# pentabug.net
KiCad netlist of a schematic drawn in EAGLE
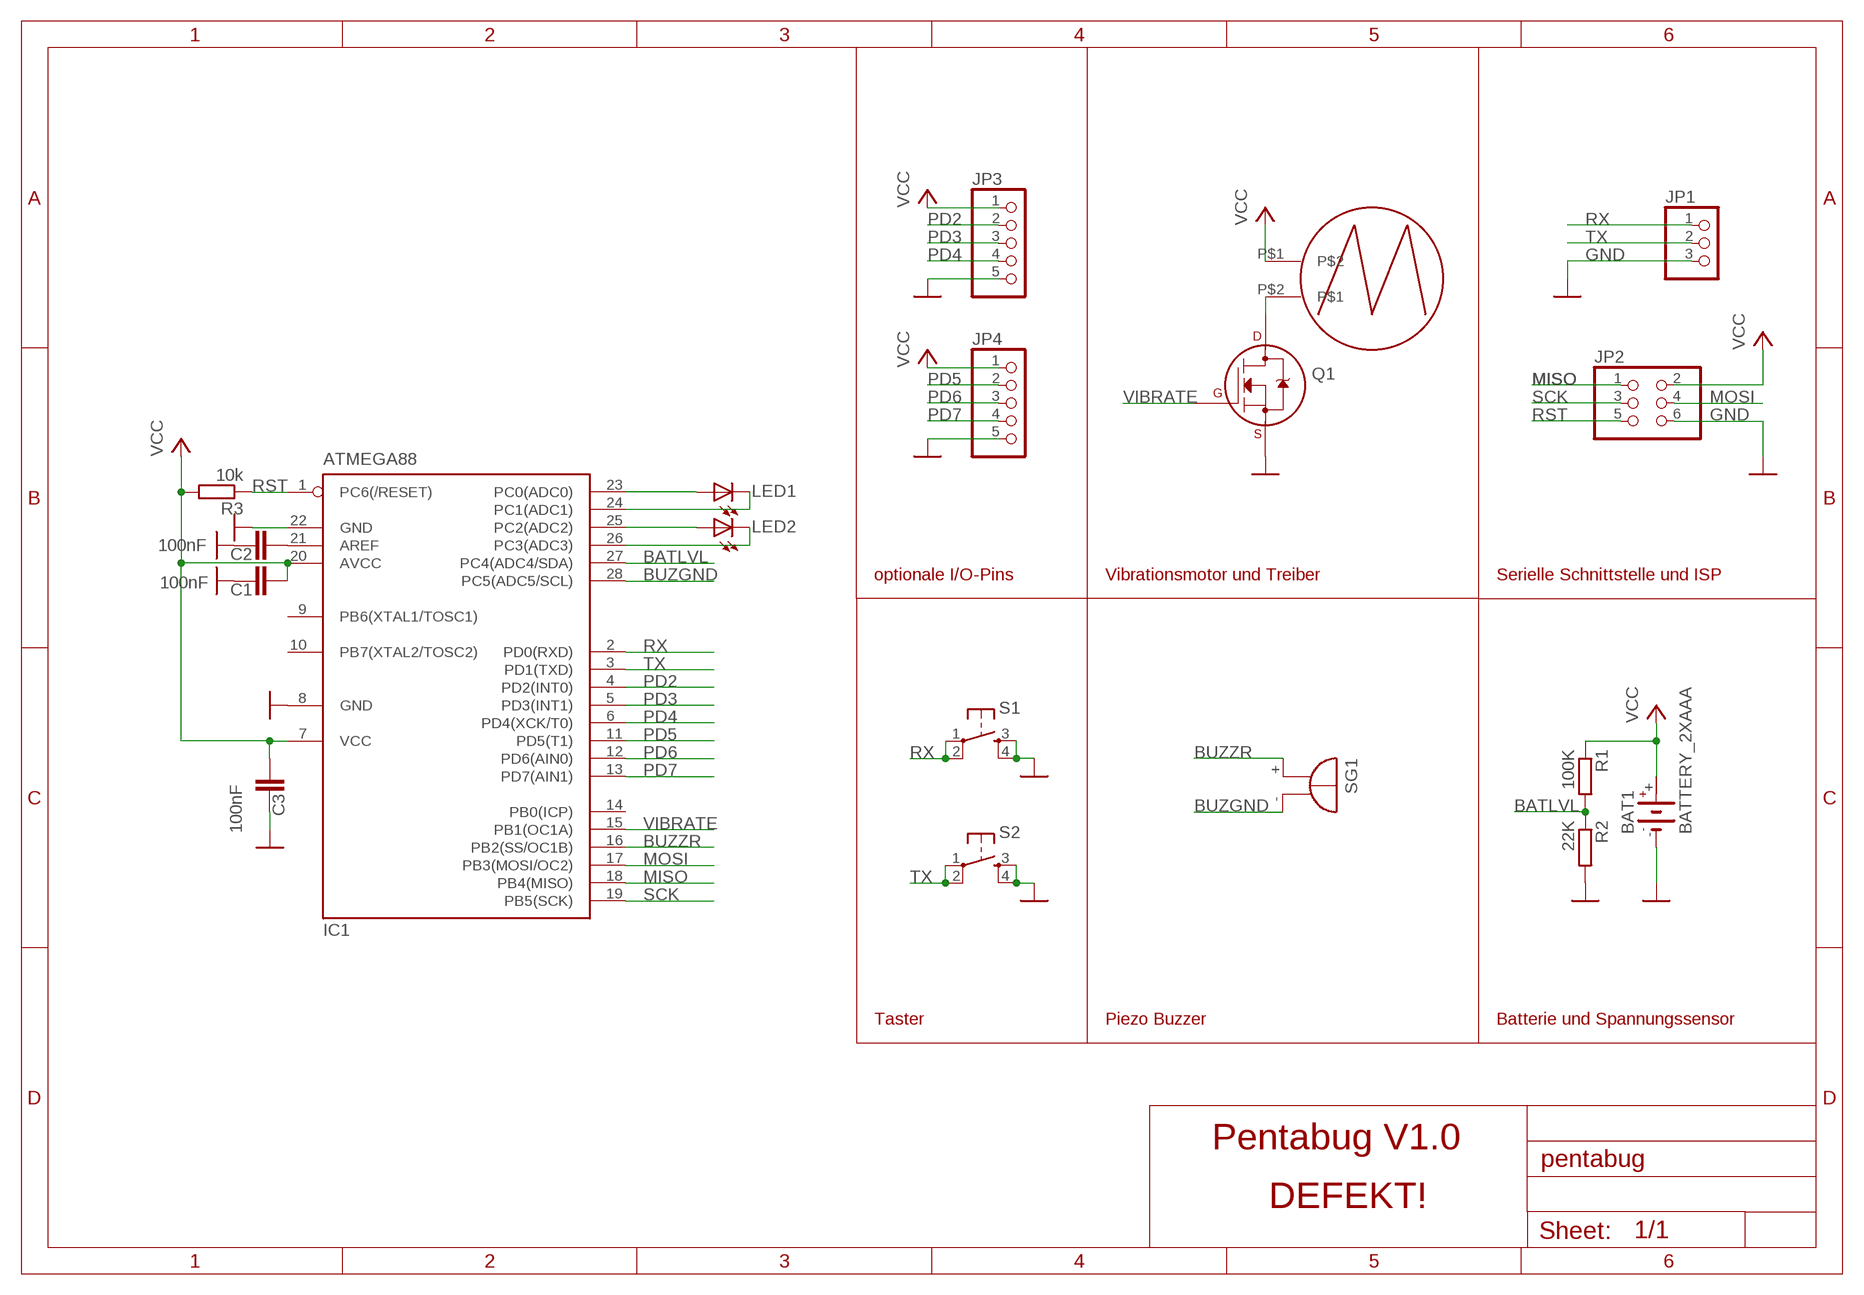
[diagram p0: schematic, sheet 1]

(export (version "E")
  (design (tool "Eeschema 10.0.6"))
  (components
    (comp (ref "BAT1")
      (value "BATTERY_2XAAA")
      (footprint "eagle-import:BATTERY_2XAAA")
      (libsource (lib "eagle-import") (part "BATTERY_2XAAA"))
    )
    (comp (ref "C1")
      (value "100nF")
      (footprint "eagle-import:C025-024X044")
      (libsource (lib "eagle-import") (part "C-EU025-024X044"))
    )
    (comp (ref "C2")
      (value "100nF")
      (footprint "eagle-import:C025-024X044")
      (libsource (lib "eagle-import") (part "C-EU025-024X044"))
    )
    (comp (ref "C3")
      (value "100nF")
      (footprint "eagle-import:C025-024X044")
      (libsource (lib "eagle-import") (part "C-EU025-024X044"))
    )
    (comp (ref "IC1")
      (value "ATMEGA88")
      (footprint "eagle-import:DIL28-3")
      (libsource (lib "eagle-import") (part "MEGA8-P"))
    )
    (comp (ref "JP1")
      (value "PINHD-1X3")
      (footprint "eagle-import:1X03")
      (libsource (lib "eagle-import") (part "PINHD-1X3"))
    )
    (comp (ref "JP2")
      (value "PINHD-2X3")
      (footprint "eagle-import:2X03")
      (libsource (lib "eagle-import") (part "PINHD-2X3"))
    )
    (comp (ref "JP3")
      (value "PINHD-1X5")
      (footprint "eagle-import:1X05")
      (libsource (lib "eagle-import") (part "PINHD-1X5"))
    )
    (comp (ref "JP4")
      (value "PINHD-1X5")
      (footprint "eagle-import:1X05")
      (libsource (lib "eagle-import") (part "PINHD-1X5"))
    )
    (comp (ref "LED1")
      (value "LED5MM")
      (footprint "eagle-import:LED5MM")
      (libsource (lib "eagle-import") (part "LED5MM"))
    )
    (comp (ref "LED2")
      (value "LED5MM")
      (footprint "eagle-import:LED5MM")
      (libsource (lib "eagle-import") (part "LED5MM"))
    )
    (comp (ref "Q1")
      (value "2N7000_TO92")
      (footprint "eagle-import:TO-92")
      (libsource (lib "eagle-import") (part "2N700_TO920"))
    )
    (comp (ref "R1")
      (value "100K")
      (footprint "eagle-import:0207_10")
      (libsource (lib "eagle-import") (part "R-EU_0207/10"))
    )
    (comp (ref "R2")
      (value "22K")
      (footprint "eagle-import:0207_10")
      (libsource (lib "eagle-import") (part "R-EU_0207/10"))
    )
    (comp (ref "R3")
      (value "10k")
      (footprint "eagle-import:0207_10")
      (libsource (lib "eagle-import") (part "R-EU_0207/10"))
    )
    (comp (ref "S1")
      (value "TAC_SWITCHPTH")
      (footprint "eagle-import:TACTILE-PTH")
      (libsource (lib "eagle-import") (part "TAC_SWITCHPTH"))
    )
    (comp (ref "S2")
      (value "TAC_SWITCHPTH")
      (footprint "eagle-import:TACTILE-PTH")
      (libsource (lib "eagle-import") (part "TAC_SWITCHPTH"))
    )
    (comp (ref "SG1")
      (value "MULTIBUZZRTDKBUZZR")
      (footprint "eagle-import:BUZZRTDK")
      (libsource (lib "eagle-import") (part "MULTIBUZZRTDKBUZZR"))
    )
    (comp (ref "U$1")
      (value "VIBRAMOTOR")
      (footprint "eagle-import:LA4-432")
      (libsource (lib "eagle-import") (part "VIBRAMOTOR"))
    )
  )
  (nets
    (net (code "1") (name "/BATLVL") (class "Default")
      (node (ref "IC1") (pin "27") (pinfunction "PC4(ADC4/SDA)_27") (pintype "bidirectional"))
      (node (ref "R1") (pin "2") (pinfunction "2_2") (pintype "passive"))
      (node (ref "R2") (pin "1") (pinfunction "1_1") (pintype "passive"))
    )
    (net (code "2") (name "/BUZGND") (class "Default")
      (node (ref "IC1") (pin "28") (pinfunction "PC5(ADC5/SCL)_28") (pintype "bidirectional"))
      (node (ref "SG1") (pin "-") (pinfunction "-_-") (pintype "passive"))
    )
    (net (code "3") (name "/BUZZR") (class "Default")
      (node (ref "IC1") (pin "16") (pinfunction "PB2(SS/OC1B)_16") (pintype "bidirectional"))
      (node (ref "SG1") (pin "+") (pinfunction "+_+") (pintype "passive"))
    )
    (net (code "4") (name "/MISO") (class "Default")
      (node (ref "IC1") (pin "18") (pinfunction "PB4(MISO)_18") (pintype "bidirectional"))
      (node (ref "JP2") (pin "1") (pinfunction "1_1") (pintype "passive"))
    )
    (net (code "5") (name "/MOSI") (class "Default")
      (node (ref "IC1") (pin "17") (pinfunction "PB3(MOSI/OC2)_17") (pintype "bidirectional"))
      (node (ref "JP2") (pin "4") (pinfunction "4_4") (pintype "passive"))
    )
    (net (code "6") (name "/PD2") (class "Default")
      (node (ref "IC1") (pin "4") (pinfunction "PD2(INT0)_4") (pintype "bidirectional"))
      (node (ref "JP3") (pin "2") (pinfunction "2_2") (pintype "passive"))
    )
    (net (code "7") (name "/PD3") (class "Default")
      (node (ref "IC1") (pin "5") (pinfunction "PD3(INT1)_5") (pintype "bidirectional"))
      (node (ref "JP3") (pin "3") (pinfunction "3_3") (pintype "passive"))
    )
    (net (code "8") (name "/PD4") (class "Default")
      (node (ref "IC1") (pin "6") (pinfunction "PD4(XCK/T0)_6") (pintype "bidirectional"))
      (node (ref "JP3") (pin "4") (pinfunction "4_4") (pintype "passive"))
    )
    (net (code "9") (name "/PD5") (class "Default")
      (node (ref "IC1") (pin "11") (pinfunction "PD5(T1)_11") (pintype "bidirectional"))
      (node (ref "JP4") (pin "2") (pinfunction "2_2") (pintype "passive"))
    )
    (net (code "10") (name "/PD6") (class "Default")
      (node (ref "IC1") (pin "12") (pinfunction "PD6(AIN0)_12") (pintype "bidirectional"))
      (node (ref "JP4") (pin "3") (pinfunction "3_3") (pintype "passive"))
    )
    (net (code "11") (name "/PD7") (class "Default")
      (node (ref "IC1") (pin "13") (pinfunction "PD7(AIN1)_13") (pintype "bidirectional"))
      (node (ref "JP4") (pin "4") (pinfunction "4_4") (pintype "passive"))
    )
    (net (code "12") (name "/RST") (class "Default")
      (node (ref "IC1") (pin "1") (pinfunction "PC6(/RESET)_1") (pintype "bidirectional"))
      (node (ref "JP2") (pin "5") (pinfunction "5_5") (pintype "passive"))
      (node (ref "R3") (pin "1") (pinfunction "1_1") (pintype "passive"))
    )
    (net (code "13") (name "/RX") (class "Default")
      (node (ref "IC1") (pin "2") (pinfunction "PD0(RXD)_2") (pintype "bidirectional"))
      (node (ref "JP1") (pin "1") (pinfunction "1_1") (pintype "passive"))
      (node (ref "S1") (pin "1") (pinfunction "1_1") (pintype "passive"))
      (node (ref "S1") (pin "2") (pinfunction "2_2") (pintype "passive"))
    )
    (net (code "14") (name "/SCK") (class "Default")
      (node (ref "IC1") (pin "19") (pinfunction "PB5(SCK)_19") (pintype "bidirectional"))
      (node (ref "JP2") (pin "3") (pinfunction "3_3") (pintype "passive"))
    )
    (net (code "15") (name "/TX") (class "Default")
      (node (ref "IC1") (pin "3") (pinfunction "PD1(TXD)_3") (pintype "bidirectional"))
      (node (ref "JP1") (pin "2") (pinfunction "2_2") (pintype "passive"))
      (node (ref "S2") (pin "1") (pinfunction "1_1") (pintype "passive"))
      (node (ref "S2") (pin "2") (pinfunction "2_2") (pintype "passive"))
    )
    (net (code "16") (name "/VIBRATE") (class "Default")
      (node (ref "IC1") (pin "15") (pinfunction "PB1(OC1A)_15") (pintype "bidirectional"))
      (node (ref "Q1") (pin "2") (pinfunction "G_2") (pintype "tri_state"))
    )
    (net (code "17") (name "GND") (class "Default")
      (node (ref "BAT1") (pin "-") (pinfunction "-_-") (pintype "passive"))
      (node (ref "C1") (pin "1") (pinfunction "1_1") (pintype "passive"))
      (node (ref "C2") (pin "1") (pinfunction "1_1") (pintype "passive"))
      (node (ref "C3") (pin "1") (pinfunction "1_1") (pintype "passive"))
      (node (ref "IC1") (pin "22") (pinfunction "GND_22") (pintype "power_in"))
      (node (ref "IC1") (pin "8") (pinfunction "GND_8") (pintype "power_in"))
      (node (ref "JP1") (pin "3") (pinfunction "3_3") (pintype "passive"))
      (node (ref "JP2") (pin "6") (pinfunction "6_6") (pintype "passive"))
      (node (ref "JP3") (pin "5") (pinfunction "5_5") (pintype "passive"))
      (node (ref "JP4") (pin "5") (pinfunction "5_5") (pintype "passive"))
      (node (ref "Q1") (pin "1") (pinfunction "S_1") (pintype "bidirectional"))
      (node (ref "R2") (pin "2") (pinfunction "2_2") (pintype "passive"))
      (node (ref "S1") (pin "3") (pinfunction "3_3") (pintype "passive"))
      (node (ref "S1") (pin "4") (pinfunction "4_4") (pintype "passive"))
      (node (ref "S2") (pin "3") (pinfunction "3_3") (pintype "passive"))
      (node (ref "S2") (pin "4") (pinfunction "4_4") (pintype "passive"))
    )
    (net (code "18") (name "Net-(IC1-AREF)") (class "Default")
      (node (ref "C2") (pin "2") (pinfunction "2_2") (pintype "passive"))
      (node (ref "IC1") (pin "21") (pinfunction "AREF_21") (pintype "passive"))
    )
    (net (code "19") (name "Net-(IC1-PC0(ADC0))") (class "Default")
      (node (ref "IC1") (pin "23") (pinfunction "PC0(ADC0)_23") (pintype "bidirectional"))
      (node (ref "LED1") (pin "A") (pinfunction "A_A") (pintype "passive"))
    )
    (net (code "20") (name "Net-(IC1-PC1(ADC1))") (class "Default")
      (node (ref "IC1") (pin "24") (pinfunction "PC1(ADC1)_24") (pintype "bidirectional"))
      (node (ref "LED1") (pin "K") (pinfunction "C_K") (pintype "passive"))
    )
    (net (code "21") (name "Net-(IC1-PC2(ADC2))") (class "Default")
      (node (ref "IC1") (pin "25") (pinfunction "PC2(ADC2)_25") (pintype "bidirectional"))
      (node (ref "LED2") (pin "A") (pinfunction "A_A") (pintype "passive"))
    )
    (net (code "22") (name "Net-(IC1-PC3(ADC3))") (class "Default")
      (node (ref "IC1") (pin "26") (pinfunction "PC3(ADC3)_26") (pintype "bidirectional"))
      (node (ref "LED2") (pin "K") (pinfunction "C_K") (pintype "passive"))
    )
    (net (code "23") (name "Net-(Q1-D)") (class "Default")
      (node (ref "Q1") (pin "3") (pinfunction "D_3") (pintype "bidirectional"))
      (node (ref "U$1") (pin "P$2") (pinfunction "P$1_P$2") (pintype "power_in"))
    )
    (net (code "24") (name "VCC") (class "Default")
      (node (ref "BAT1") (pin "+") (pinfunction "+_+") (pintype "passive"))
      (node (ref "C1") (pin "2") (pinfunction "2_2") (pintype "passive"))
      (node (ref "C3") (pin "2") (pinfunction "2_2") (pintype "passive"))
      (node (ref "IC1") (pin "20") (pinfunction "AVCC_20") (pintype "power_in"))
      (node (ref "IC1") (pin "7") (pinfunction "VCC_7") (pintype "power_in"))
      (node (ref "JP2") (pin "2") (pinfunction "2_2") (pintype "passive"))
      (node (ref "JP3") (pin "1") (pinfunction "1_1") (pintype "passive"))
      (node (ref "JP4") (pin "1") (pinfunction "1_1") (pintype "passive"))
      (node (ref "R1") (pin "1") (pinfunction "1_1") (pintype "passive"))
      (node (ref "R3") (pin "2") (pinfunction "2_2") (pintype "passive"))
      (node (ref "U$1") (pin "P$1") (pinfunction "P$2_P$1") (pintype "power_in"))
    )
    (net (code "25") (name "unconnected-(IC1-PB0(ICP)-Pad14)") (class "Default")
      (node (ref "IC1") (pin "14") (pinfunction "PB0(ICP)_14") (pintype "bidirectional"))
    )
    (net (code "26") (name "unconnected-(IC1-PB6(XTAL1{slash}TOSC1)-Pad9)") (class "Default")
      (node (ref "IC1") (pin "9") (pinfunction "PB6(XTAL1/TOSC1)_9") (pintype "bidirectional"))
    )
    (net (code "27") (name "unconnected-(IC1-PB7(XTAL2{slash}TOSC2)-Pad10)") (class "Default")
      (node (ref "IC1") (pin "10") (pinfunction "PB7(XTAL2/TOSC2)_10") (pintype "bidirectional"))
    )
  )
)
